# LM2596.net
KiCad netlist of a schematic drawn in Altium Designer
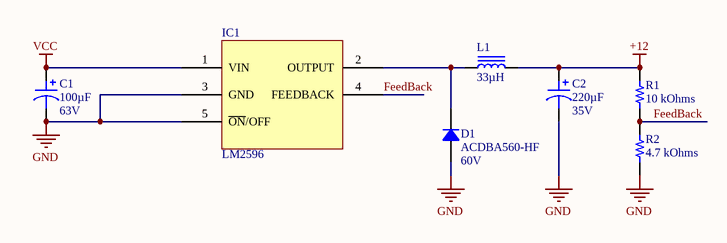
[diagram p0: LM2596.SchDoc]

(export (version "E")
  (design (tool "Eeschema 10.0.6"))
  (components
    (comp (ref "C1")
      (value "100µF")
      (footprint "CAP TH ALUM ELEC D8.00mm S3.50mm H12.50mm")
      (description "CAP ALUM 100UF 20% 63V RADIAL")
      (fields
        (field (name "PART NUMBER") "ECA-1JM101")
        (field (name "MANUFACTURER") "Panasonic Electronic Components")
        (field (name "VOLTAGE - RATED") "63V")
      )
      (libsource (lib "Celestial Altium Library - altium_library") (part "Polarised Capacitor"))
    )
    (comp (ref "C2")
      (value "220µF")
      (footprint "CAP TH ALUM ELEC D8.00mm S3.50mm H12.50mm")
      (description "CAP ALUM 220UF 20% 35V RADIAL")
      (fields
        (field (name "PART NUMBER") "ECA-1VM221")
        (field (name "MANUFACTURER") "Panasonic Electronic Components")
        (field (name "VOLTAGE - RATED") "35V")
      )
      (libsource (lib "Celestial Altium Library - altium_library") (part "Polarised Capacitor"))
    )
    (comp (ref "D1")
      (value "ACDBA560-HF")
      (footprint "DO214AC SMA")
      (description "DIODE SCHOTTKY 60V 5A DO214AC")
      (fields
        (field (name "MANUFACTURER") "Comchip Technology")
        (field (name "VOLTAGE - DC REVERSE (VR) (MAX)") "60V")
      )
      (libsource (lib "Celestial Altium Library - altium_library") (part "Diode"))
    )
    (comp (ref "IC1")
      (value "LM2596")
      (footprint "AltiumLive:D2PAK")
      (libsource (lib "AltiumLive") (part "LM2596"))
    )
    (comp (ref "L1")
      (value "33µH")
      (footprint "BOURNS SRR1280")
      (description "FIXED IND 33UH 3.5A 57 MOHM SMD")
      (fields (field (name "PART NUMBER") "SRR1280-330M") (field (name "MANUFACTURER") "Bourns Inc."))
      (libsource (lib "Celestial Altium Library - altium_library") (part "Inductor"))
    )
    (comp (ref "R1")
      (value "10 kOhms")
      (footprint "RES 0805_2012")
      (description "RES 10K OHM 1% 1/4W 0805")
      (fields
        (field (name "PART NUMBER") "RNCP0805FTD10K0")
        (field (name "MANUFACTURER") "Stackpole Electronics Inc")
      )
      (libsource (lib "Celestial Altium Library - altium_library") (part "Resistor"))
    )
    (comp (ref "R2")
      (value "4.7 kOhms")
      (footprint "RES 0805_2012")
      (description "CRGP 0805 4K7 1%")
      (fields
        (field (name "PART NUMBER") "CRGP0805F4K7")
        (field (name "MANUFACTURER") "TE Connectivity Passive Product")
      )
      (libsource (lib "Celestial Altium Library - altium_library") (part "Resistor"))
    )
  )
  (nets
    (net (code "1") (name "+12") (class "Default")
      (node (ref "C2") (pin "1") (pinfunction "1_1") (pintype "passive"))
      (node (ref "L1") (pin "2") (pinfunction "2_2") (pintype "passive"))
      (node (ref "R1") (pin "2") (pinfunction "2_2") (pintype "passive"))
    )
    (net (code "2") (name "/FeedBack") (class "Default")
      (node (ref "IC1") (pin "4") (pinfunction "FEEDBACK_4") (pintype "passive"))
      (node (ref "R1") (pin "1") (pinfunction "1_1") (pintype "passive"))
      (node (ref "R2") (pin "2") (pinfunction "2_2") (pintype "passive"))
    )
    (net (code "3") (name "GND") (class "Default")
      (node (ref "C1") (pin "2") (pinfunction "2_2") (pintype "passive"))
      (node (ref "C2") (pin "2") (pinfunction "2_2") (pintype "passive"))
      (node (ref "D1") (pin "1") (pinfunction "1_1") (pintype "passive"))
      (node (ref "IC1") (pin "3") (pinfunction "GND_3") (pintype "passive"))
      (node (ref "IC1") (pin "5") (pinfunction "~{ON}/OFF_5") (pintype "passive"))
      (node (ref "R2") (pin "1") (pinfunction "1_1") (pintype "passive"))
    )
    (net (code "4") (name "Net-(IC1-OUTPUT)") (class "Default")
      (node (ref "D1") (pin "2") (pinfunction "2_2") (pintype "passive"))
      (node (ref "IC1") (pin "2") (pinfunction "OUTPUT_2") (pintype "passive"))
      (node (ref "L1") (pin "1") (pinfunction "1_1") (pintype "passive"))
    )
    (net (code "5") (name "VCC") (class "Default")
      (node (ref "C1") (pin "1") (pinfunction "1_1") (pintype "passive"))
      (node (ref "IC1") (pin "1") (pinfunction "VIN_1") (pintype "passive"))
    )
  )
)
